# LEDMatrix.net
KiCad netlist of a schematic drawn in EAGLE
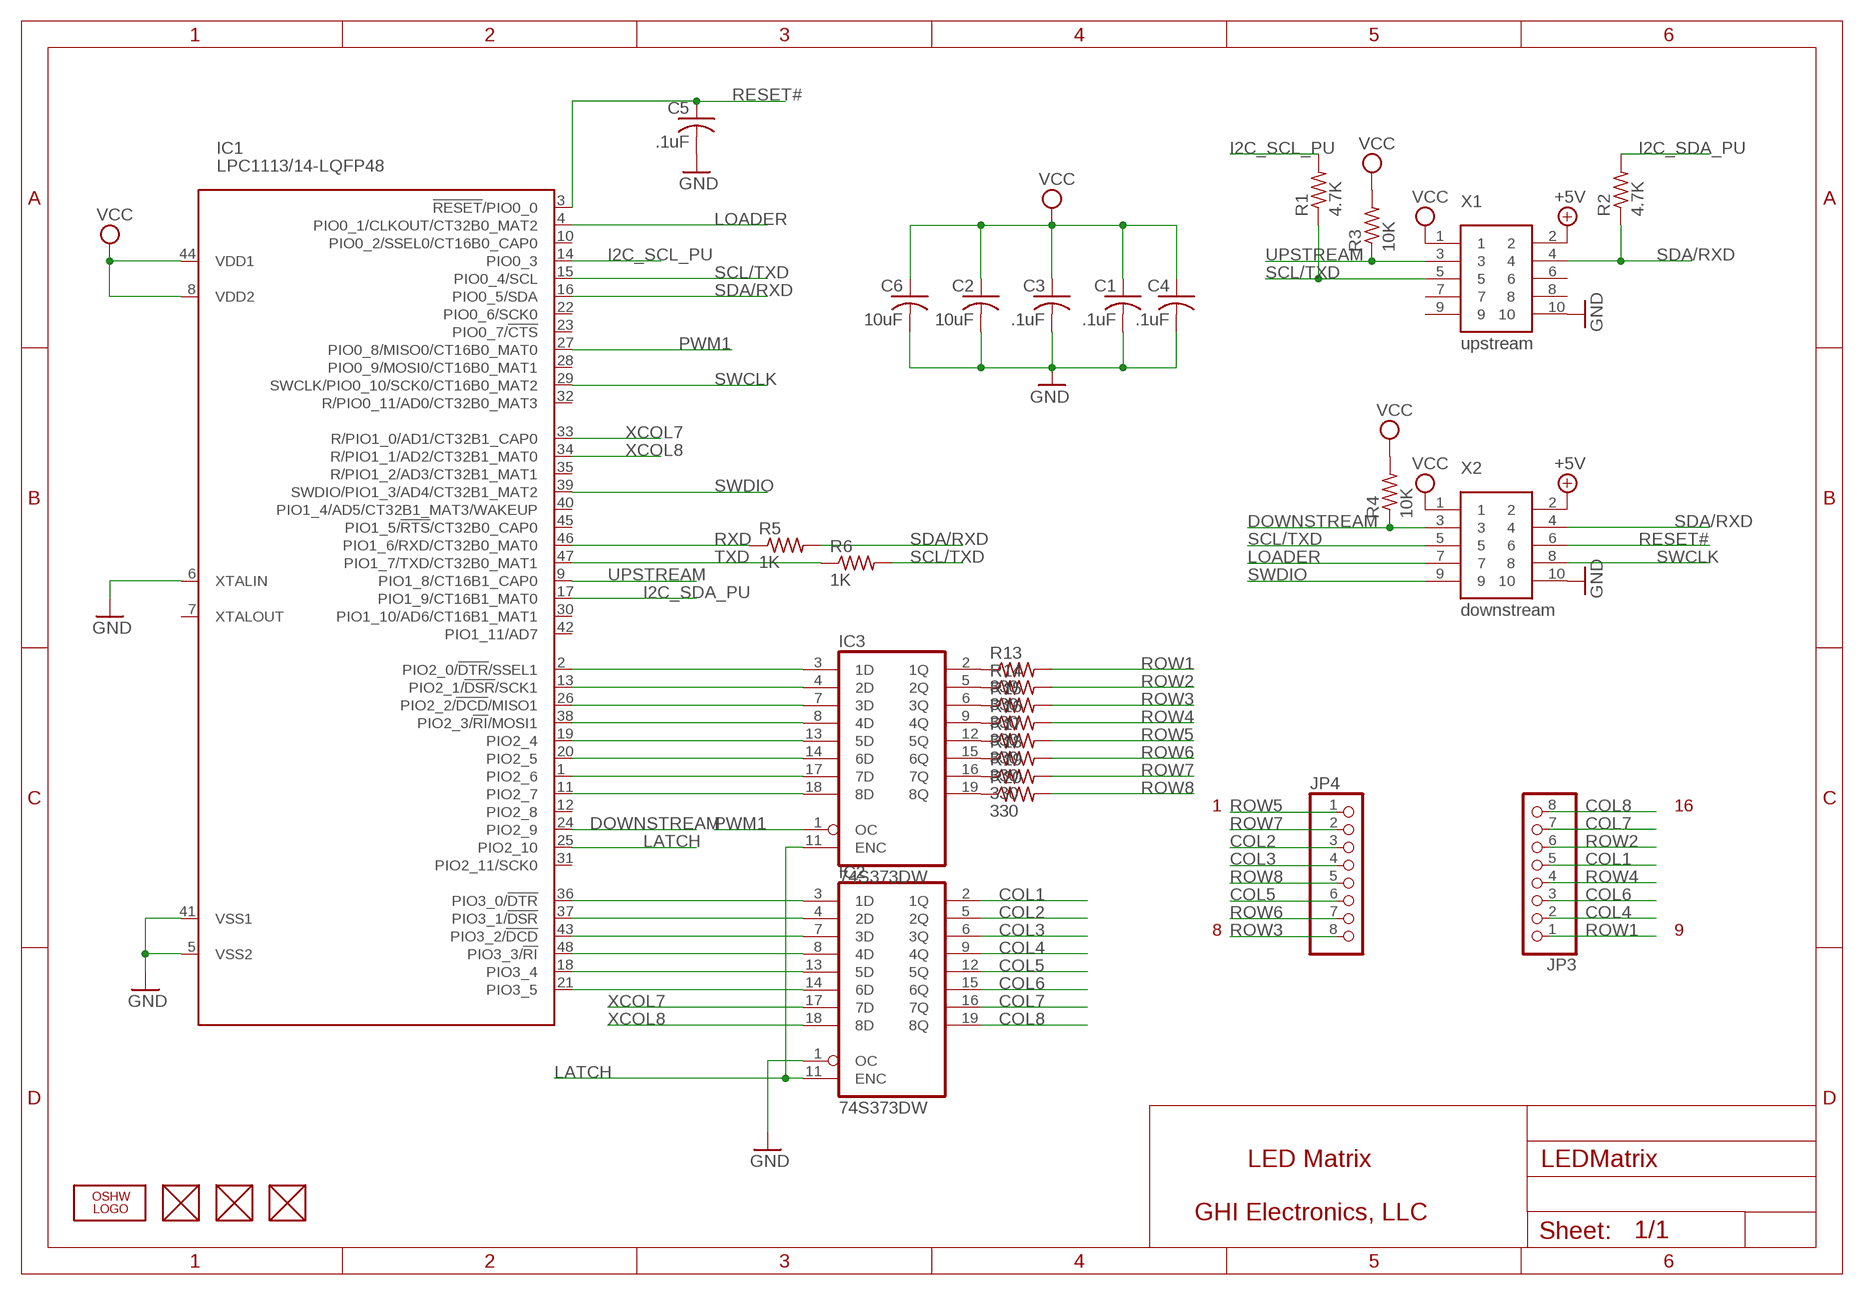
[diagram p0: schematic, sheet 1]

(export (version "E")
  (design (tool "Eeschema 10.0.6"))
  (components
    (comp (ref "C1")
      (value ".1uF")
      (footprint "eagle-import:C0603K")
      (libsource (lib "eagle-import") (part "C-USC0603K"))
    )
    (comp (ref "C2")
      (value "10uF")
      (footprint "eagle-import:C0805K")
      (libsource (lib "eagle-import") (part "C-USC0805K"))
    )
    (comp (ref "C3")
      (value ".1uF")
      (footprint "eagle-import:C0603K")
      (libsource (lib "eagle-import") (part "C-USC0603K"))
    )
    (comp (ref "C4")
      (value ".1uF")
      (footprint "eagle-import:C0603K")
      (libsource (lib "eagle-import") (part "C-USC0603K"))
    )
    (comp (ref "C5")
      (value ".1uF")
      (footprint "eagle-import:C0603K")
      (libsource (lib "eagle-import") (part "C-USC0603K"))
    )
    (comp (ref "C6")
      (value "10uF")
      (footprint "eagle-import:C0805K")
      (libsource (lib "eagle-import") (part "C-USC0805K"))
    )
    (comp (ref "FUD1")
      (value "FIDUCIAL")
      (footprint "eagle-import:FIDUCIAL_40MIL")
      (libsource (lib "eagle-import") (part "FIDUCIAL"))
    )
    (comp (ref "FUD2")
      (value "FIDUCIAL")
      (footprint "eagle-import:FIDUCIAL_40MIL")
      (libsource (lib "eagle-import") (part "FIDUCIAL"))
    )
    (comp (ref "FUD3")
      (value "FIDUCIAL")
      (footprint "eagle-import:FIDUCIAL_40MIL")
      (libsource (lib "eagle-import") (part "FIDUCIAL"))
    )
    (comp (ref "IC1")
      (value "LPC1113/14-LQFP48")
      (footprint "eagle-import:LQFP48")
      (libsource (lib "eagle-import") (part "LPC1113/14-LQFP48"))
    )
    (comp (ref "IC2")
      (value "74S373DW")
      (footprint "eagle-import:SO20W")
      (libsource (lib "eagle-import") (part "74373DWS"))
    )
    (comp (ref "IC3")
      (value "74S373DW")
      (footprint "eagle-import:SO20W")
      (libsource (lib "eagle-import") (part "74373DWS"))
    )
    (comp (ref "JP3")
      (value "PINHD-1X8")
      (footprint "eagle-import:1X08")
      (libsource (lib "eagle-import") (part "PINHD-1X8"))
    )
    (comp (ref "JP4")
      (value "PINHD-1X8")
      (footprint "eagle-import:1X08")
      (libsource (lib "eagle-import") (part "PINHD-1X8"))
    )
    (comp (ref "LOGO")
      (value "LOGO-OSHW-FILLX0200-NT")
      (footprint "eagle-import:OSHW_FILLX200_NOTEXT")
      (libsource (lib "eagle-import") (part "LOGO-OSHW-FILLX0200-NT"))
    )
    (comp (ref "R1")
      (value "4.7K")
      (footprint "eagle-import:R0603")
      (libsource (lib "eagle-import") (part "R-US_R0603"))
    )
    (comp (ref "R2")
      (value "4.7K")
      (footprint "eagle-import:R0603")
      (libsource (lib "eagle-import") (part "R-US_R0603"))
    )
    (comp (ref "R3")
      (value "10K")
      (footprint "eagle-import:R0603")
      (libsource (lib "eagle-import") (part "R-US_R0603"))
    )
    (comp (ref "R4")
      (value "10K")
      (footprint "eagle-import:R0603")
      (libsource (lib "eagle-import") (part "R-US_R0603"))
    )
    (comp (ref "R5")
      (value "1K")
      (footprint "eagle-import:R0603")
      (libsource (lib "eagle-import") (part "R-US_R0603"))
    )
    (comp (ref "R6")
      (value "1K")
      (footprint "eagle-import:R0603")
      (libsource (lib "eagle-import") (part "R-US_R0603"))
    )
    (comp (ref "R13")
      (value "330")
      (footprint "eagle-import:R0603")
      (libsource (lib "eagle-import") (part "R-US_R0603"))
    )
    (comp (ref "R14")
      (value "330")
      (footprint "eagle-import:R0603")
      (libsource (lib "eagle-import") (part "R-US_R0603"))
    )
    (comp (ref "R15")
      (value "330")
      (footprint "eagle-import:R0603")
      (libsource (lib "eagle-import") (part "R-US_R0603"))
    )
    (comp (ref "R16")
      (value "330")
      (footprint "eagle-import:R0603")
      (libsource (lib "eagle-import") (part "R-US_R0603"))
    )
    (comp (ref "R17")
      (value "330")
      (footprint "eagle-import:R0603")
      (libsource (lib "eagle-import") (part "R-US_R0603"))
    )
    (comp (ref "R18")
      (value "330")
      (footprint "eagle-import:R0603")
      (libsource (lib "eagle-import") (part "R-US_R0603"))
    )
    (comp (ref "R19")
      (value "330")
      (footprint "eagle-import:R0603")
      (libsource (lib "eagle-import") (part "R-US_R0603"))
    )
    (comp (ref "R20")
      (value "330")
      (footprint "eagle-import:R0603")
      (libsource (lib "eagle-import") (part "R-US_R0603"))
    )
    (comp (ref "X1")
      (value "upstream")
      (footprint "eagle-import:2X5_1.27MM")
      (libsource (lib "eagle-import") (part "2X5_1.27MM"))
    )
    (comp (ref "X2")
      (value "downstream")
      (footprint "eagle-import:2X5_1.27MM")
      (libsource (lib "eagle-import") (part "2X5_1.27MM"))
    )
  )
  (nets
    (net (code "1") (name "+5V") (class "Default")
      (node (ref "X1") (pin "2") (pinfunction "2_2") (pintype "bidirectional"))
      (node (ref "X2") (pin "2") (pinfunction "2_2") (pintype "bidirectional"))
    )
    (net (code "2") (name "/COL1") (class "Default")
      (node (ref "IC2") (pin "2") (pinfunction "1Q_2") (pintype "tri_state"))
      (node (ref "JP3") (pin "5") (pinfunction "5_5") (pintype "passive"))
    )
    (net (code "3") (name "/COL2") (class "Default")
      (node (ref "IC2") (pin "5") (pinfunction "2Q_5") (pintype "tri_state"))
      (node (ref "JP4") (pin "3") (pinfunction "3_3") (pintype "passive"))
    )
    (net (code "4") (name "/COL3") (class "Default")
      (node (ref "IC2") (pin "6") (pinfunction "3Q_6") (pintype "tri_state"))
      (node (ref "JP4") (pin "4") (pinfunction "4_4") (pintype "passive"))
    )
    (net (code "5") (name "/COL4") (class "Default")
      (node (ref "IC2") (pin "9") (pinfunction "4Q_9") (pintype "tri_state"))
      (node (ref "JP3") (pin "2") (pinfunction "2_2") (pintype "passive"))
    )
    (net (code "6") (name "/COL5") (class "Default")
      (node (ref "IC2") (pin "12") (pinfunction "5Q_12") (pintype "tri_state"))
      (node (ref "JP4") (pin "6") (pinfunction "6_6") (pintype "passive"))
    )
    (net (code "7") (name "/COL6") (class "Default")
      (node (ref "IC2") (pin "15") (pinfunction "6Q_15") (pintype "tri_state"))
      (node (ref "JP3") (pin "3") (pinfunction "3_3") (pintype "passive"))
    )
    (net (code "8") (name "/COL7") (class "Default")
      (node (ref "IC2") (pin "16") (pinfunction "7Q_16") (pintype "tri_state"))
      (node (ref "JP3") (pin "7") (pinfunction "7_7") (pintype "passive"))
    )
    (net (code "9") (name "/COL8") (class "Default")
      (node (ref "IC2") (pin "19") (pinfunction "8Q_19") (pintype "tri_state"))
      (node (ref "JP3") (pin "8") (pinfunction "8_8") (pintype "passive"))
    )
    (net (code "10") (name "/DOWNSTREAM") (class "Default")
      (node (ref "IC1") (pin "24") (pinfunction "PIO2_9_24") (pintype "bidirectional"))
      (node (ref "R4") (pin "1") (pinfunction "1_1") (pintype "passive"))
      (node (ref "X2") (pin "3") (pinfunction "3_3") (pintype "bidirectional"))
    )
    (net (code "11") (name "/I2C_SCL_PU") (class "Default")
      (node (ref "IC1") (pin "14") (pinfunction "PIO0_3_14") (pintype "bidirectional"))
      (node (ref "R1") (pin "2") (pinfunction "2_2") (pintype "passive"))
    )
    (net (code "12") (name "/I2C_SDA_PU") (class "Default")
      (node (ref "IC1") (pin "17") (pinfunction "PIO1_9/CT16B1_MAT0_17") (pintype "bidirectional"))
      (node (ref "R2") (pin "2") (pinfunction "2_2") (pintype "passive"))
    )
    (net (code "13") (name "/LATCH") (class "Default")
      (node (ref "IC1") (pin "25") (pinfunction "PIO2_10_25") (pintype "bidirectional"))
      (node (ref "IC2") (pin "11") (pinfunction "ENC_11") (pintype "input"))
      (node (ref "IC3") (pin "11") (pinfunction "ENC_11") (pintype "input"))
    )
    (net (code "14") (name "/LOADER") (class "Default")
      (node (ref "IC1") (pin "4") (pinfunction "PIO0_1/CLKOUT/CT32B0_MAT2_4") (pintype "bidirectional"))
      (node (ref "X2") (pin "7") (pinfunction "7_7") (pintype "bidirectional"))
    )
    (net (code "15") (name "/PWM1") (class "Default")
      (node (ref "IC1") (pin "27") (pinfunction "PIO0_8/MISO0/CT16B0_MAT0_27") (pintype "bidirectional"))
      (node (ref "IC3") (pin "1") (pinfunction "OC_1") (pintype "input"))
    )
    (net (code "16") (name "/RESET#") (class "Default")
      (node (ref "C5") (pin "1") (pinfunction "1_1") (pintype "passive"))
      (node (ref "IC1") (pin "3") (pinfunction "~{RESET}/PIO0_0_3") (pintype "bidirectional"))
      (node (ref "X2") (pin "6") (pinfunction "6_6") (pintype "bidirectional"))
    )
    (net (code "17") (name "/ROW1") (class "Default")
      (node (ref "JP3") (pin "1") (pinfunction "1_1") (pintype "passive"))
      (node (ref "R13") (pin "2") (pinfunction "2_2") (pintype "passive"))
    )
    (net (code "18") (name "/ROW2") (class "Default")
      (node (ref "JP3") (pin "6") (pinfunction "6_6") (pintype "passive"))
      (node (ref "R14") (pin "2") (pinfunction "2_2") (pintype "passive"))
    )
    (net (code "19") (name "/ROW3") (class "Default")
      (node (ref "JP4") (pin "8") (pinfunction "8_8") (pintype "passive"))
      (node (ref "R15") (pin "2") (pinfunction "2_2") (pintype "passive"))
    )
    (net (code "20") (name "/ROW4") (class "Default")
      (node (ref "JP3") (pin "4") (pinfunction "4_4") (pintype "passive"))
      (node (ref "R16") (pin "2") (pinfunction "2_2") (pintype "passive"))
    )
    (net (code "21") (name "/ROW5") (class "Default")
      (node (ref "JP4") (pin "1") (pinfunction "1_1") (pintype "passive"))
      (node (ref "R17") (pin "2") (pinfunction "2_2") (pintype "passive"))
    )
    (net (code "22") (name "/ROW6") (class "Default")
      (node (ref "JP4") (pin "7") (pinfunction "7_7") (pintype "passive"))
      (node (ref "R18") (pin "2") (pinfunction "2_2") (pintype "passive"))
    )
    (net (code "23") (name "/ROW7") (class "Default")
      (node (ref "JP4") (pin "2") (pinfunction "2_2") (pintype "passive"))
      (node (ref "R19") (pin "2") (pinfunction "2_2") (pintype "passive"))
    )
    (net (code "24") (name "/ROW8") (class "Default")
      (node (ref "JP4") (pin "5") (pinfunction "5_5") (pintype "passive"))
      (node (ref "R20") (pin "2") (pinfunction "2_2") (pintype "passive"))
    )
    (net (code "25") (name "/RXD") (class "Default")
      (node (ref "IC1") (pin "46") (pinfunction "PIO1_6/RXD/CT32B0_MAT0_46") (pintype "bidirectional"))
      (node (ref "R5") (pin "1") (pinfunction "1_1") (pintype "passive"))
    )
    (net (code "26") (name "/SCL{slash}TXD") (class "Default")
      (node (ref "IC1") (pin "15") (pinfunction "PIO0_4/SCL_15") (pintype "bidirectional"))
      (node (ref "R1") (pin "1") (pinfunction "1_1") (pintype "passive"))
      (node (ref "R6") (pin "2") (pinfunction "2_2") (pintype "passive"))
      (node (ref "X1") (pin "5") (pinfunction "5_5") (pintype "bidirectional"))
      (node (ref "X2") (pin "5") (pinfunction "5_5") (pintype "bidirectional"))
    )
    (net (code "27") (name "/SDA{slash}RXD") (class "Default")
      (node (ref "IC1") (pin "16") (pinfunction "PIO0_5/SDA_16") (pintype "bidirectional"))
      (node (ref "R2") (pin "1") (pinfunction "1_1") (pintype "passive"))
      (node (ref "R5") (pin "2") (pinfunction "2_2") (pintype "passive"))
      (node (ref "X1") (pin "4") (pinfunction "4_4") (pintype "bidirectional"))
      (node (ref "X2") (pin "4") (pinfunction "4_4") (pintype "bidirectional"))
    )
    (net (code "28") (name "/SWCLK") (class "Default")
      (node (ref "IC1") (pin "29") (pinfunction "SWCLK/PIO0_10/SCK0/CT16B0_MAT2_29") (pintype "bidirectional"))
      (node (ref "X2") (pin "8") (pinfunction "8_8") (pintype "bidirectional"))
    )
    (net (code "29") (name "/SWDIO") (class "Default")
      (node (ref "IC1") (pin "39") (pinfunction "SWDIO/PIO1_3/AD4/CT32B1_MAT2_39") (pintype "bidirectional"))
      (node (ref "X2") (pin "9") (pinfunction "9_9") (pintype "bidirectional"))
    )
    (net (code "30") (name "/TXD") (class "Default")
      (node (ref "IC1") (pin "47") (pinfunction "PIO1_7/TXD/CT32B0_MAT1_47") (pintype "bidirectional"))
      (node (ref "R6") (pin "1") (pinfunction "1_1") (pintype "passive"))
    )
    (net (code "31") (name "/UPSTREAM") (class "Default")
      (node (ref "IC1") (pin "9") (pinfunction "PIO1_8/CT16B1_CAP0_9") (pintype "bidirectional"))
      (node (ref "R3") (pin "1") (pinfunction "1_1") (pintype "passive"))
      (node (ref "X1") (pin "3") (pinfunction "3_3") (pintype "bidirectional"))
    )
    (net (code "32") (name "/XCOL7") (class "Default")
      (node (ref "IC1") (pin "33") (pinfunction "R/PIO1_0/AD1/CT32B1_CAP0_33") (pintype "bidirectional"))
      (node (ref "IC2") (pin "17") (pinfunction "7D_17") (pintype "input"))
    )
    (net (code "33") (name "/XCOL8") (class "Default")
      (node (ref "IC1") (pin "34") (pinfunction "R/PIO1_1/AD2/CT32B1_MAT0_34") (pintype "bidirectional"))
      (node (ref "IC2") (pin "18") (pinfunction "8D_18") (pintype "input"))
    )
    (net (code "34") (name "GND") (class "Default")
      (node (ref "C1") (pin "2") (pinfunction "2_2") (pintype "passive"))
      (node (ref "C2") (pin "2") (pinfunction "2_2") (pintype "passive"))
      (node (ref "C3") (pin "2") (pinfunction "2_2") (pintype "passive"))
      (node (ref "C4") (pin "2") (pinfunction "2_2") (pintype "passive"))
      (node (ref "C5") (pin "2") (pinfunction "2_2") (pintype "passive"))
      (node (ref "C6") (pin "2") (pinfunction "2_2") (pintype "passive"))
      (node (ref "IC1") (pin "41") (pinfunction "VSS1_41") (pintype "power_in"))
      (node (ref "IC1") (pin "5") (pinfunction "VSS2_5") (pintype "power_in"))
      (node (ref "IC1") (pin "6") (pinfunction "XTALIN_6") (pintype "passive"))
      (node (ref "IC2") (pin "1") (pinfunction "OC_1") (pintype "input"))
      (node (ref "X1") (pin "10") (pinfunction "10_10") (pintype "bidirectional"))
      (node (ref "X2") (pin "10") (pinfunction "10_10") (pintype "bidirectional"))
    )
    (net (code "35") (name "Net-(IC1-PIO2_0{slash}~{DTR}{slash}SSEL1)") (class "Default")
      (node (ref "IC1") (pin "2") (pinfunction "PIO2_0/~{DTR}/SSEL1_2") (pintype "bidirectional"))
      (node (ref "IC3") (pin "3") (pinfunction "1D_3") (pintype "input"))
    )
    (net (code "36") (name "Net-(IC1-PIO2_1{slash}~{DSR}{slash}SCK1)") (class "Default")
      (node (ref "IC1") (pin "13") (pinfunction "PIO2_1/~{DSR}/SCK1_13") (pintype "bidirectional"))
      (node (ref "IC3") (pin "4") (pinfunction "2D_4") (pintype "input"))
    )
    (net (code "37") (name "Net-(IC1-PIO2_2{slash}~{DCD}{slash}MISO1)") (class "Default")
      (node (ref "IC1") (pin "26") (pinfunction "PIO2_2/~{DCD}/MISO1_26") (pintype "bidirectional"))
      (node (ref "IC3") (pin "7") (pinfunction "3D_7") (pintype "input"))
    )
    (net (code "38") (name "Net-(IC1-PIO2_3{slash}~{RI}{slash}MOSI1)") (class "Default")
      (node (ref "IC1") (pin "38") (pinfunction "PIO2_3/~{RI}/MOSI1_38") (pintype "bidirectional"))
      (node (ref "IC3") (pin "8") (pinfunction "4D_8") (pintype "input"))
    )
    (net (code "39") (name "Net-(IC1-PIO2_4)") (class "Default")
      (node (ref "IC1") (pin "19") (pinfunction "PIO2_4_19") (pintype "bidirectional"))
      (node (ref "IC3") (pin "13") (pinfunction "5D_13") (pintype "input"))
    )
    (net (code "40") (name "Net-(IC1-PIO2_5)") (class "Default")
      (node (ref "IC1") (pin "20") (pinfunction "PIO2_5_20") (pintype "bidirectional"))
      (node (ref "IC3") (pin "14") (pinfunction "6D_14") (pintype "input"))
    )
    (net (code "41") (name "Net-(IC1-PIO2_6)") (class "Default")
      (node (ref "IC1") (pin "1") (pinfunction "PIO2_6_1") (pintype "bidirectional"))
      (node (ref "IC3") (pin "17") (pinfunction "7D_17") (pintype "input"))
    )
    (net (code "42") (name "Net-(IC1-PIO2_7)") (class "Default")
      (node (ref "IC1") (pin "11") (pinfunction "PIO2_7_11") (pintype "bidirectional"))
      (node (ref "IC3") (pin "18") (pinfunction "8D_18") (pintype "input"))
    )
    (net (code "43") (name "Net-(IC1-PIO3_0{slash}~{DTR})") (class "Default")
      (node (ref "IC1") (pin "36") (pinfunction "PIO3_0/~{DTR}_36") (pintype "bidirectional"))
      (node (ref "IC2") (pin "3") (pinfunction "1D_3") (pintype "input"))
    )
    (net (code "44") (name "Net-(IC1-PIO3_1{slash}~{DSR})") (class "Default")
      (node (ref "IC1") (pin "37") (pinfunction "PIO3_1/~{DSR}_37") (pintype "bidirectional"))
      (node (ref "IC2") (pin "4") (pinfunction "2D_4") (pintype "input"))
    )
    (net (code "45") (name "Net-(IC1-PIO3_2{slash}~{DCD})") (class "Default")
      (node (ref "IC1") (pin "43") (pinfunction "PIO3_2/~{DCD}_43") (pintype "bidirectional"))
      (node (ref "IC2") (pin "7") (pinfunction "3D_7") (pintype "input"))
    )
    (net (code "46") (name "Net-(IC1-PIO3_3{slash}~{RI})") (class "Default")
      (node (ref "IC1") (pin "48") (pinfunction "PIO3_3/~{RI}_48") (pintype "bidirectional"))
      (node (ref "IC2") (pin "8") (pinfunction "4D_8") (pintype "input"))
    )
    (net (code "47") (name "Net-(IC1-PIO3_4)") (class "Default")
      (node (ref "IC1") (pin "18") (pinfunction "PIO3_4_18") (pintype "bidirectional"))
      (node (ref "IC2") (pin "13") (pinfunction "5D_13") (pintype "input"))
    )
    (net (code "48") (name "Net-(IC1-PIO3_5)") (class "Default")
      (node (ref "IC1") (pin "21") (pinfunction "PIO3_5_21") (pintype "bidirectional"))
      (node (ref "IC2") (pin "14") (pinfunction "6D_14") (pintype "input"))
    )
    (net (code "49") (name "Net-(IC3A-1Q)") (class "Default")
      (node (ref "IC3") (pin "2") (pinfunction "1Q_2") (pintype "tri_state"))
      (node (ref "R13") (pin "1") (pinfunction "1_1") (pintype "passive"))
    )
    (net (code "50") (name "Net-(IC3A-2Q)") (class "Default")
      (node (ref "IC3") (pin "5") (pinfunction "2Q_5") (pintype "tri_state"))
      (node (ref "R14") (pin "1") (pinfunction "1_1") (pintype "passive"))
    )
    (net (code "51") (name "Net-(IC3A-3Q)") (class "Default")
      (node (ref "IC3") (pin "6") (pinfunction "3Q_6") (pintype "tri_state"))
      (node (ref "R15") (pin "1") (pinfunction "1_1") (pintype "passive"))
    )
    (net (code "52") (name "Net-(IC3A-4Q)") (class "Default")
      (node (ref "IC3") (pin "9") (pinfunction "4Q_9") (pintype "tri_state"))
      (node (ref "R16") (pin "1") (pinfunction "1_1") (pintype "passive"))
    )
    (net (code "53") (name "Net-(IC3A-5Q)") (class "Default")
      (node (ref "IC3") (pin "12") (pinfunction "5Q_12") (pintype "tri_state"))
      (node (ref "R17") (pin "1") (pinfunction "1_1") (pintype "passive"))
    )
    (net (code "54") (name "Net-(IC3A-6Q)") (class "Default")
      (node (ref "IC3") (pin "15") (pinfunction "6Q_15") (pintype "tri_state"))
      (node (ref "R18") (pin "1") (pinfunction "1_1") (pintype "passive"))
    )
    (net (code "55") (name "Net-(IC3A-7Q)") (class "Default")
      (node (ref "IC3") (pin "16") (pinfunction "7Q_16") (pintype "tri_state"))
      (node (ref "R19") (pin "1") (pinfunction "1_1") (pintype "passive"))
    )
    (net (code "56") (name "Net-(IC3A-8Q)") (class "Default")
      (node (ref "IC3") (pin "19") (pinfunction "8Q_19") (pintype "tri_state"))
      (node (ref "R20") (pin "1") (pinfunction "1_1") (pintype "passive"))
    )
    (net (code "57") (name "VCC") (class "Default")
      (node (ref "C1") (pin "1") (pinfunction "1_1") (pintype "passive"))
      (node (ref "C2") (pin "1") (pinfunction "1_1") (pintype "passive"))
      (node (ref "C3") (pin "1") (pinfunction "1_1") (pintype "passive"))
      (node (ref "C4") (pin "1") (pinfunction "1_1") (pintype "passive"))
      (node (ref "C6") (pin "1") (pinfunction "1_1") (pintype "passive"))
      (node (ref "IC1") (pin "44") (pinfunction "VDD1_44") (pintype "power_in"))
      (node (ref "IC1") (pin "8") (pinfunction "VDD2_8") (pintype "power_in"))
      (node (ref "R3") (pin "2") (pinfunction "2_2") (pintype "passive"))
      (node (ref "R4") (pin "2") (pinfunction "2_2") (pintype "passive"))
      (node (ref "X1") (pin "1") (pinfunction "1_1") (pintype "bidirectional"))
      (node (ref "X2") (pin "1") (pinfunction "1_1") (pintype "bidirectional"))
    )
    (net (code "58") (name "unconnected-(FUD1-PadP$1)") (class "Default")
      (node (ref "FUD1") (pin "P$1") (pinfunction "P$1_P$1") (pintype "no_connect"))
    )
    (net (code "59") (name "unconnected-(FUD2-PadP$1)") (class "Default")
      (node (ref "FUD2") (pin "P$1") (pinfunction "P$1_P$1") (pintype "no_connect"))
    )
    (net (code "60") (name "unconnected-(FUD3-PadP$1)") (class "Default")
      (node (ref "FUD3") (pin "P$1") (pinfunction "P$1_P$1") (pintype "no_connect"))
    )
    (net (code "61") (name "unconnected-(IC1-PIO0_2{slash}SSEL0{slash}CT16B0_CAP0-Pad10)") (class "Default")
      (node (ref "IC1") (pin "10") (pinfunction "PIO0_2/SSEL0/CT16B0_CAP0_10") (pintype "bidirectional"))
    )
    (net (code "62") (name "unconnected-(IC1-PIO0_6{slash}SCK0-Pad22)") (class "Default")
      (node (ref "IC1") (pin "22") (pinfunction "PIO0_6/SCK0_22") (pintype "bidirectional"))
    )
    (net (code "63") (name "unconnected-(IC1-PIO0_7{slash}~{CTS}-Pad23)") (class "Default")
      (node (ref "IC1") (pin "23") (pinfunction "PIO0_7/~{CTS}_23") (pintype "bidirectional"))
    )
    (net (code "64") (name "unconnected-(IC1-PIO0_9{slash}MOSI0{slash}CT16B0_MAT1-Pad28)") (class "Default")
      (node (ref "IC1") (pin "28") (pinfunction "PIO0_9/MOSI0/CT16B0_MAT1_28") (pintype "bidirectional"))
    )
    (net (code "65") (name "unconnected-(IC1-PIO1_4{slash}AD5{slash}CT32B1_MAT3{slash}WAKEUP-Pad40)") (class "Default")
      (node (ref "IC1") (pin "40") (pinfunction "PIO1_4/AD5/CT32B1_MAT3/WAKEUP_40") (pintype "bidirectional"))
    )
    (net (code "66") (name "unconnected-(IC1-PIO1_5{slash}~{RTS}{slash}CT32B0_CAP0-Pad45)") (class "Default")
      (node (ref "IC1") (pin "45") (pinfunction "PIO1_5/~{RTS}/CT32B0_CAP0_45") (pintype "bidirectional"))
    )
    (net (code "67") (name "unconnected-(IC1-PIO1_10{slash}AD6{slash}CT16B1_MAT1-Pad30)") (class "Default")
      (node (ref "IC1") (pin "30") (pinfunction "PIO1_10/AD6/CT16B1_MAT1_30") (pintype "bidirectional"))
    )
    (net (code "68") (name "unconnected-(IC1-PIO1_11{slash}AD7-Pad42)") (class "Default")
      (node (ref "IC1") (pin "42") (pinfunction "PIO1_11/AD7_42") (pintype "bidirectional"))
    )
    (net (code "69") (name "unconnected-(IC1-PIO2_8-Pad12)") (class "Default")
      (node (ref "IC1") (pin "12") (pinfunction "PIO2_8_12") (pintype "bidirectional"))
    )
    (net (code "70") (name "unconnected-(IC1-PIO2_11{slash}SCK0-Pad31)") (class "Default")
      (node (ref "IC1") (pin "31") (pinfunction "PIO2_11/SCK0_31") (pintype "bidirectional"))
    )
    (net (code "71") (name "unconnected-(IC1-R{slash}PIO0_11{slash}AD0{slash}CT32B0_MAT3-Pad32)") (class "Default")
      (node (ref "IC1") (pin "32") (pinfunction "R/PIO0_11/AD0/CT32B0_MAT3_32") (pintype "bidirectional"))
    )
    (net (code "72") (name "unconnected-(IC1-R{slash}PIO1_2{slash}AD3{slash}CT32B1_MAT1-Pad35)") (class "Default")
      (node (ref "IC1") (pin "35") (pinfunction "R/PIO1_2/AD3/CT32B1_MAT1_35") (pintype "bidirectional"))
    )
    (net (code "73") (name "unconnected-(IC1-XTALOUT-Pad7)") (class "Default")
      (node (ref "IC1") (pin "7") (pinfunction "XTALOUT_7") (pintype "passive"))
    )
    (net (code "74") (name "unconnected-(X1-Pad6)") (class "Default")
      (node (ref "X1") (pin "6") (pinfunction "6_6") (pintype "bidirectional"))
    )
    (net (code "75") (name "unconnected-(X1-Pad7)") (class "Default")
      (node (ref "X1") (pin "7") (pinfunction "7_7") (pintype "bidirectional"))
    )
    (net (code "76") (name "unconnected-(X1-Pad8)") (class "Default")
      (node (ref "X1") (pin "8") (pinfunction "8_8") (pintype "bidirectional"))
    )
    (net (code "77") (name "unconnected-(X1-Pad9)") (class "Default")
      (node (ref "X1") (pin "9") (pinfunction "9_9") (pintype "bidirectional"))
    )
  )
)
